# Control.net
KiCad netlist of a schematic drawn in EAGLE
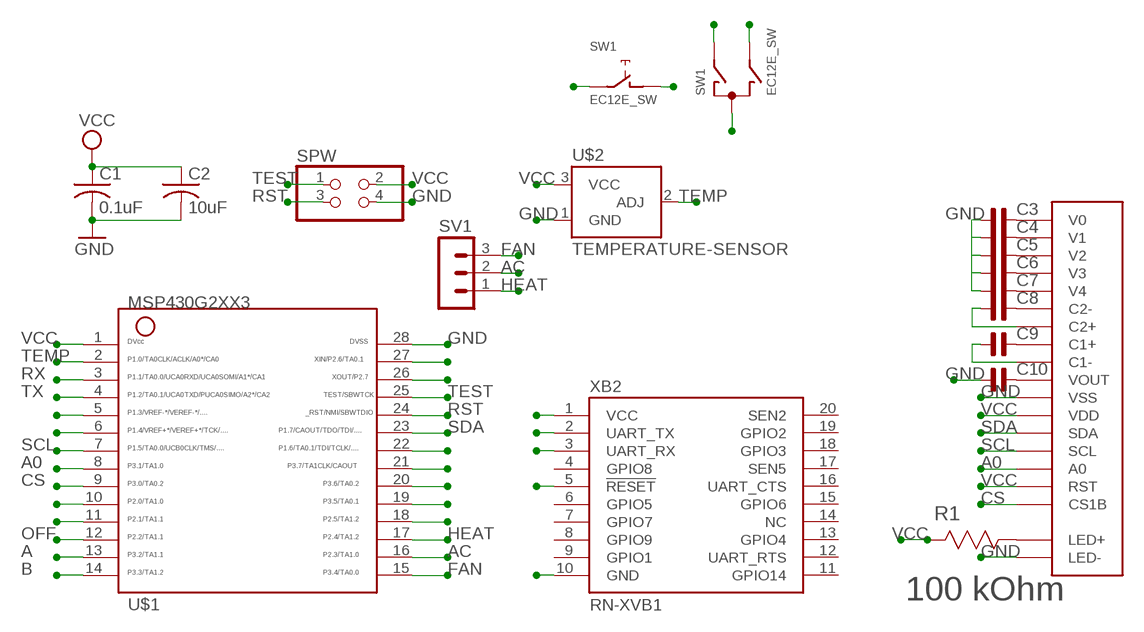
[diagram p0: schematic, sheet 1]

(export (version "E")
  (design (tool "Eeschema 10.0.6"))
  (components
    (comp (ref "C1")
      (value "0.1uF")
      (footprint "eagle-import:C0603K")
      (libsource (lib "eagle-import") (part "C-USC0603K"))
    )
    (comp (ref "C2")
      (value "10uF")
      (footprint "eagle-import:C0603K")
      (libsource (lib "eagle-import") (part "C-USC0603K"))
    )
    (comp (ref "C3")
      (value "C-NP-SMD-0603")
      (footprint "eagle-import:C-0603")
      (libsource (lib "eagle-import") (part "C-NP-SMD-0603"))
    )
    (comp (ref "C4")
      (value "C-NP-SMD-0603")
      (footprint "eagle-import:C-0603")
      (libsource (lib "eagle-import") (part "C-NP-SMD-0603"))
    )
    (comp (ref "C5")
      (value "C-NP-SMD-0603")
      (footprint "eagle-import:C-0603")
      (libsource (lib "eagle-import") (part "C-NP-SMD-0603"))
    )
    (comp (ref "C6")
      (value "C-NP-SMD-0603")
      (footprint "eagle-import:C-0603")
      (libsource (lib "eagle-import") (part "C-NP-SMD-0603"))
    )
    (comp (ref "C7")
      (value "C-NP-SMD-0603")
      (footprint "eagle-import:C-0603")
      (libsource (lib "eagle-import") (part "C-NP-SMD-0603"))
    )
    (comp (ref "C8")
      (value "C-NP-SMD-0603")
      (footprint "eagle-import:C-0603")
      (libsource (lib "eagle-import") (part "C-NP-SMD-0603"))
    )
    (comp (ref "C9")
      (value "C-NP-SMD-0603")
      (footprint "eagle-import:C-0603")
      (libsource (lib "eagle-import") (part "C-NP-SMD-0603"))
    )
    (comp (ref "C10")
      (value "C-NP-SMD-0603")
      (footprint "eagle-import:C-0603")
      (libsource (lib "eagle-import") (part "C-NP-SMD-0603"))
    )
    (comp (ref "R1")
      (value "100 kOhm")
      (footprint "eagle-import:RESC1608X60N")
      (fields (field (name "MPN") "ERA-3AEB104V") (field (name "TOLERANCE") "±0.1%"))
      (libsource (lib "eagle-import") (part "ERA-3AEB104V"))
    )
    (comp (ref "SPW")
      (value "PINHD-2X2")
      (footprint "eagle-import:2X02")
      (libsource (lib "eagle-import") (part "PINHD-2X2"))
    )
    (comp (ref "SV1")
      (value "MA03-1")
      (footprint "eagle-import:MA03-1")
      (libsource (lib "eagle-import") (part "MA03-1"))
    )
    (comp (ref "SW1")
      (value "EC12E_SW")
      (footprint "eagle-import:ALPS_EC12E_SW")
      (fields (field (name "MPN") "EC12E2424407"))
      (libsource (lib "eagle-import") (part "EC12E_SW"))
    )
    (comp (ref "U$1")
      (value "G2XX3---PW28")
      (footprint "eagle-import:PW28")
      (libsource (lib "eagle-import") (part "G2XX3---PW28"))
    )
    (comp (ref "U$2")
      (value "TEMPERATURE-SENSOR")
      (footprint "eagle-import:TO-92")
      (libsource (lib "eagle-import") (part "TEMPERATURE-SENSOR"))
    )
    (comp (ref "U$3")
      (value "NHD-C12832A1Z-FSW-FBW-3V3")
      (footprint "eagle-import:NHD-C12832A1Z-FSW-FBW-3V3")
      (libsource (lib "eagle-import") (part "NHD-C12832A1Z-FSW-FBW-3V3"))
    )
    (comp (ref "XB2")
      (value "RN-XVB1")
      (footprint "eagle-import:XBEE")
      (libsource (lib "eagle-import") (part "RN-XVB1"))
    )
  )
  (nets
    (net (code "1") (name "/A") (class "Default")
      (node (ref "SW1") (pin "B") (pinfunction "B_B") (pintype "passive"))
      (node (ref "U$1") (pin "13") (pinfunction "13_13") (pintype "bidirectional"))
    )
    (net (code "2") (name "/A0") (class "Default")
      (node (ref "U$1") (pin "8") (pinfunction "8_8") (pintype "bidirectional"))
      (node (ref "U$3") (pin "15") (pinfunction "A0_15") (pintype "bidirectional"))
    )
    (net (code "3") (name "/AC") (class "Default")
      (node (ref "SV1") (pin "2") (pinfunction "2_2") (pintype "passive"))
      (node (ref "U$1") (pin "16") (pinfunction "16_16") (pintype "bidirectional"))
    )
    (net (code "4") (name "/B") (class "Default")
      (node (ref "SW1") (pin "A") (pinfunction "A_A") (pintype "passive"))
      (node (ref "U$1") (pin "14") (pinfunction "14_14") (pintype "bidirectional"))
    )
    (net (code "5") (name "/CS") (class "Default")
      (node (ref "U$1") (pin "9") (pinfunction "9_9") (pintype "bidirectional"))
      (node (ref "U$3") (pin "17") (pinfunction "CS1B_17") (pintype "bidirectional"))
    )
    (net (code "6") (name "/FAN") (class "Default")
      (node (ref "SV1") (pin "3") (pinfunction "3_3") (pintype "passive"))
      (node (ref "U$1") (pin "15") (pinfunction "15_15") (pintype "bidirectional"))
    )
    (net (code "7") (name "/HEAT") (class "Default")
      (node (ref "SV1") (pin "1") (pinfunction "1_1") (pintype "passive"))
      (node (ref "U$1") (pin "17") (pinfunction "17_17") (pintype "bidirectional"))
    )
    (net (code "8") (name "/OFF") (class "Default")
      (node (ref "SW1") (pin "E") (pinfunction "2_E") (pintype "passive"))
      (node (ref "U$1") (pin "12") (pinfunction "12_12") (pintype "bidirectional"))
    )
    (net (code "9") (name "/RST") (class "Default")
      (node (ref "SPW") (pin "3") (pinfunction "3_3") (pintype "passive"))
      (node (ref "U$1") (pin "24") (pinfunction "24_24") (pintype "bidirectional"))
    )
    (net (code "10") (name "/RX") (class "Default")
      (node (ref "U$1") (pin "3") (pinfunction "3_3") (pintype "bidirectional"))
      (node (ref "XB2") (pin "2") (pinfunction "UART_TX_2") (pintype "output"))
    )
    (net (code "11") (name "/SCL") (class "Default")
      (node (ref "U$1") (pin "7") (pinfunction "7_7") (pintype "bidirectional"))
      (node (ref "U$3") (pin "14") (pinfunction "SCL_14") (pintype "bidirectional"))
    )
    (net (code "12") (name "/SDA") (class "Default")
      (node (ref "U$1") (pin "23") (pinfunction "23_23") (pintype "bidirectional"))
      (node (ref "U$3") (pin "13") (pinfunction "SDA_13") (pintype "bidirectional"))
    )
    (net (code "13") (name "/TEMP") (class "Default")
      (node (ref "U$1") (pin "2") (pinfunction "2_2") (pintype "bidirectional"))
      (node (ref "U$2") (pin "2") (pinfunction "ADJ_2") (pintype "bidirectional"))
    )
    (net (code "14") (name "/TEST") (class "Default")
      (node (ref "SPW") (pin "1") (pinfunction "1_1") (pintype "passive"))
      (node (ref "U$1") (pin "25") (pinfunction "25_25") (pintype "bidirectional"))
    )
    (net (code "15") (name "/TX") (class "Default")
      (node (ref "U$1") (pin "4") (pinfunction "4_4") (pintype "bidirectional"))
      (node (ref "XB2") (pin "3") (pinfunction "UART_RX_3") (pintype "input"))
    )
    (net (code "16") (name "GND") (class "Default")
      (node (ref "C1") (pin "2") (pinfunction "2_2") (pintype "passive"))
      (node (ref "C10") (pin "1") (pinfunction "1_1") (pintype "passive"))
      (node (ref "C2") (pin "2") (pinfunction "2_2") (pintype "passive"))
      (node (ref "C3") (pin "1") (pinfunction "1_1") (pintype "passive"))
      (node (ref "C4") (pin "1") (pinfunction "1_1") (pintype "passive"))
      (node (ref "C5") (pin "1") (pinfunction "1_1") (pintype "passive"))
      (node (ref "C6") (pin "1") (pinfunction "1_1") (pintype "passive"))
      (node (ref "C7") (pin "1") (pinfunction "1_1") (pintype "passive"))
      (node (ref "SPW") (pin "4") (pinfunction "4_4") (pintype "passive"))
      (node (ref "SW1") (pin "C") (pinfunction "C_C") (pintype "passive"))
      (node (ref "U$1") (pin "28") (pinfunction "28_28") (pintype "bidirectional"))
      (node (ref "U$2") (pin "1") (pinfunction "GND_1") (pintype "bidirectional"))
      (node (ref "U$3") (pin "11") (pinfunction "VSS_11") (pintype "bidirectional"))
      (node (ref "U$3") (pin "K") (pinfunction "LED-_K") (pintype "bidirectional"))
      (node (ref "XB2") (pin "10") (pinfunction "GND_10") (pintype "power_in"))
    )
    (net (code "17") (name "Net-(R1-R1)") (class "Default")
      (node (ref "R1") (pin "1") (pinfunction "R1_1") (pintype "passive"))
      (node (ref "U$3") (pin "A") (pinfunction "LED+_A") (pintype "bidirectional"))
    )
    (net (code "18") (name "Net-(U$3-C1+)") (class "Default")
      (node (ref "C9") (pin "2") (pinfunction "2_2") (pintype "passive"))
      (node (ref "U$3") (pin "8") (pinfunction "C1+_8") (pintype "bidirectional"))
    )
    (net (code "19") (name "Net-(U$3-C1-)") (class "Default")
      (node (ref "C9") (pin "1") (pinfunction "1_1") (pintype "passive"))
      (node (ref "U$3") (pin "9") (pinfunction "C1-_9") (pintype "bidirectional"))
    )
    (net (code "20") (name "Net-(U$3-C2+)") (class "Default")
      (node (ref "C8") (pin "1") (pinfunction "1_1") (pintype "passive"))
      (node (ref "U$3") (pin "7") (pinfunction "C2+_7") (pintype "bidirectional"))
    )
    (net (code "21") (name "Net-(U$3-C2-)") (class "Default")
      (node (ref "C8") (pin "2") (pinfunction "2_2") (pintype "passive"))
      (node (ref "U$3") (pin "6") (pinfunction "C2-_6") (pintype "bidirectional"))
    )
    (net (code "22") (name "Net-(U$3-V0)") (class "Default")
      (node (ref "C3") (pin "2") (pinfunction "2_2") (pintype "passive"))
      (node (ref "U$3") (pin "1") (pinfunction "V0_1") (pintype "bidirectional"))
    )
    (net (code "23") (name "Net-(U$3-V1)") (class "Default")
      (node (ref "C4") (pin "2") (pinfunction "2_2") (pintype "passive"))
      (node (ref "U$3") (pin "2") (pinfunction "V1_2") (pintype "bidirectional"))
    )
    (net (code "24") (name "Net-(U$3-V2)") (class "Default")
      (node (ref "C5") (pin "2") (pinfunction "2_2") (pintype "passive"))
      (node (ref "U$3") (pin "3") (pinfunction "V2_3") (pintype "bidirectional"))
    )
    (net (code "25") (name "Net-(U$3-V3)") (class "Default")
      (node (ref "C6") (pin "2") (pinfunction "2_2") (pintype "passive"))
      (node (ref "U$3") (pin "4") (pinfunction "V3_4") (pintype "bidirectional"))
    )
    (net (code "26") (name "Net-(U$3-V4)") (class "Default")
      (node (ref "C7") (pin "2") (pinfunction "2_2") (pintype "passive"))
      (node (ref "U$3") (pin "5") (pinfunction "V4_5") (pintype "bidirectional"))
    )
    (net (code "27") (name "Net-(U$3-VOUT)") (class "Default")
      (node (ref "C10") (pin "2") (pinfunction "2_2") (pintype "passive"))
      (node (ref "U$3") (pin "10") (pinfunction "VOUT_10") (pintype "bidirectional"))
    )
    (net (code "28") (name "VCC") (class "Default")
      (node (ref "C1") (pin "1") (pinfunction "1_1") (pintype "passive"))
      (node (ref "C2") (pin "1") (pinfunction "1_1") (pintype "passive"))
      (node (ref "R1") (pin "2") (pinfunction "R2_2") (pintype "passive"))
      (node (ref "SPW") (pin "2") (pinfunction "2_2") (pintype "passive"))
      (node (ref "SW1") (pin "D") (pinfunction "1_D") (pintype "passive"))
      (node (ref "U$1") (pin "1") (pinfunction "1_1") (pintype "bidirectional"))
      (node (ref "U$2") (pin "3") (pinfunction "VCC_3") (pintype "bidirectional"))
      (node (ref "U$3") (pin "12") (pinfunction "VDD_12") (pintype "bidirectional"))
      (node (ref "U$3") (pin "16") (pinfunction "RST_16") (pintype "bidirectional"))
      (node (ref "XB2") (pin "1") (pinfunction "VCC_1") (pintype "power_in"))
      (node (ref "XB2") (pin "5") (pinfunction "~{RESET}_5") (pintype "input"))
    )
    (net (code "29") (name "unconnected-(U$1-Pad5)") (class "Default")
      (node (ref "U$1") (pin "5") (pinfunction "5_5") (pintype "bidirectional"))
    )
    (net (code "30") (name "unconnected-(U$1-Pad6)") (class "Default")
      (node (ref "U$1") (pin "6") (pinfunction "6_6") (pintype "bidirectional"))
    )
    (net (code "31") (name "unconnected-(U$1-Pad10)") (class "Default")
      (node (ref "U$1") (pin "10") (pinfunction "10_10") (pintype "bidirectional"))
    )
    (net (code "32") (name "unconnected-(U$1-Pad11)") (class "Default")
      (node (ref "U$1") (pin "11") (pinfunction "11_11") (pintype "bidirectional"))
    )
    (net (code "33") (name "unconnected-(U$1-Pad18)") (class "Default")
      (node (ref "U$1") (pin "18") (pinfunction "18_18") (pintype "bidirectional"))
    )
    (net (code "34") (name "unconnected-(U$1-Pad19)") (class "Default")
      (node (ref "U$1") (pin "19") (pinfunction "19_19") (pintype "bidirectional"))
    )
    (net (code "35") (name "unconnected-(U$1-Pad20)") (class "Default")
      (node (ref "U$1") (pin "20") (pinfunction "20_20") (pintype "bidirectional"))
    )
    (net (code "36") (name "unconnected-(U$1-Pad21)") (class "Default")
      (node (ref "U$1") (pin "21") (pinfunction "21_21") (pintype "bidirectional"))
    )
    (net (code "37") (name "unconnected-(U$1-Pad22)") (class "Default")
      (node (ref "U$1") (pin "22") (pinfunction "22_22") (pintype "bidirectional"))
    )
    (net (code "38") (name "unconnected-(U$1-Pad26)") (class "Default")
      (node (ref "U$1") (pin "26") (pinfunction "26_26") (pintype "bidirectional"))
    )
    (net (code "39") (name "unconnected-(U$1-Pad27)") (class "Default")
      (node (ref "U$1") (pin "27") (pinfunction "27_27") (pintype "bidirectional"))
    )
    (net (code "40") (name "unconnected-(XB2-GPIO1-Pad9)") (class "Default")
      (node (ref "XB2") (pin "9") (pinfunction "GPIO1_9") (pintype "bidirectional"))
    )
    (net (code "41") (name "unconnected-(XB2-GPIO2-Pad19)") (class "Default")
      (node (ref "XB2") (pin "19") (pinfunction "GPIO2_19") (pintype "bidirectional"))
    )
    (net (code "42") (name "unconnected-(XB2-GPIO3-Pad18)") (class "Default")
      (node (ref "XB2") (pin "18") (pinfunction "GPIO3_18") (pintype "bidirectional"))
    )
    (net (code "43") (name "unconnected-(XB2-GPIO4-Pad13)") (class "Default")
      (node (ref "XB2") (pin "13") (pinfunction "GPIO4_13") (pintype "bidirectional"))
    )
    (net (code "44") (name "unconnected-(XB2-GPIO5-Pad6)") (class "Default")
      (node (ref "XB2") (pin "6") (pinfunction "GPIO5_6") (pintype "bidirectional"))
    )
    (net (code "45") (name "unconnected-(XB2-GPIO6-Pad15)") (class "Default")
      (node (ref "XB2") (pin "15") (pinfunction "GPIO6_15") (pintype "bidirectional"))
    )
    (net (code "46") (name "unconnected-(XB2-GPIO7-Pad7)") (class "Default")
      (node (ref "XB2") (pin "7") (pinfunction "GPIO7_7") (pintype "bidirectional"))
    )
    (net (code "47") (name "unconnected-(XB2-GPIO8-Pad4)") (class "Default")
      (node (ref "XB2") (pin "4") (pinfunction "GPIO8_4") (pintype "bidirectional"))
    )
    (net (code "48") (name "unconnected-(XB2-GPIO9-Pad8)") (class "Default")
      (node (ref "XB2") (pin "8") (pinfunction "GPIO9_8") (pintype "bidirectional"))
    )
    (net (code "49") (name "unconnected-(XB2-GPIO14-Pad11)") (class "Default")
      (node (ref "XB2") (pin "11") (pinfunction "GPIO14_11") (pintype "bidirectional"))
    )
    (net (code "50") (name "unconnected-(XB2-NC-Pad14)") (class "Default")
      (node (ref "XB2") (pin "14") (pinfunction "NC_14") (pintype "no_connect"))
    )
    (net (code "51") (name "unconnected-(XB2-SEN2-Pad20)") (class "Default")
      (node (ref "XB2") (pin "20") (pinfunction "SEN2_20") (pintype "bidirectional"))
    )
    (net (code "52") (name "unconnected-(XB2-SEN5-Pad17)") (class "Default")
      (node (ref "XB2") (pin "17") (pinfunction "SEN5_17") (pintype "bidirectional"))
    )
    (net (code "53") (name "unconnected-(XB2-UART_CTS-Pad16)") (class "Default")
      (node (ref "XB2") (pin "16") (pinfunction "UART_CTS_16") (pintype "input"))
    )
    (net (code "54") (name "unconnected-(XB2-UART_RTS-Pad12)") (class "Default")
      (node (ref "XB2") (pin "12") (pinfunction "UART_RTS_12") (pintype "output"))
    )
  )
)
